# Sheet2.net
KiCad netlist of a schematic drawn in Altium Designer
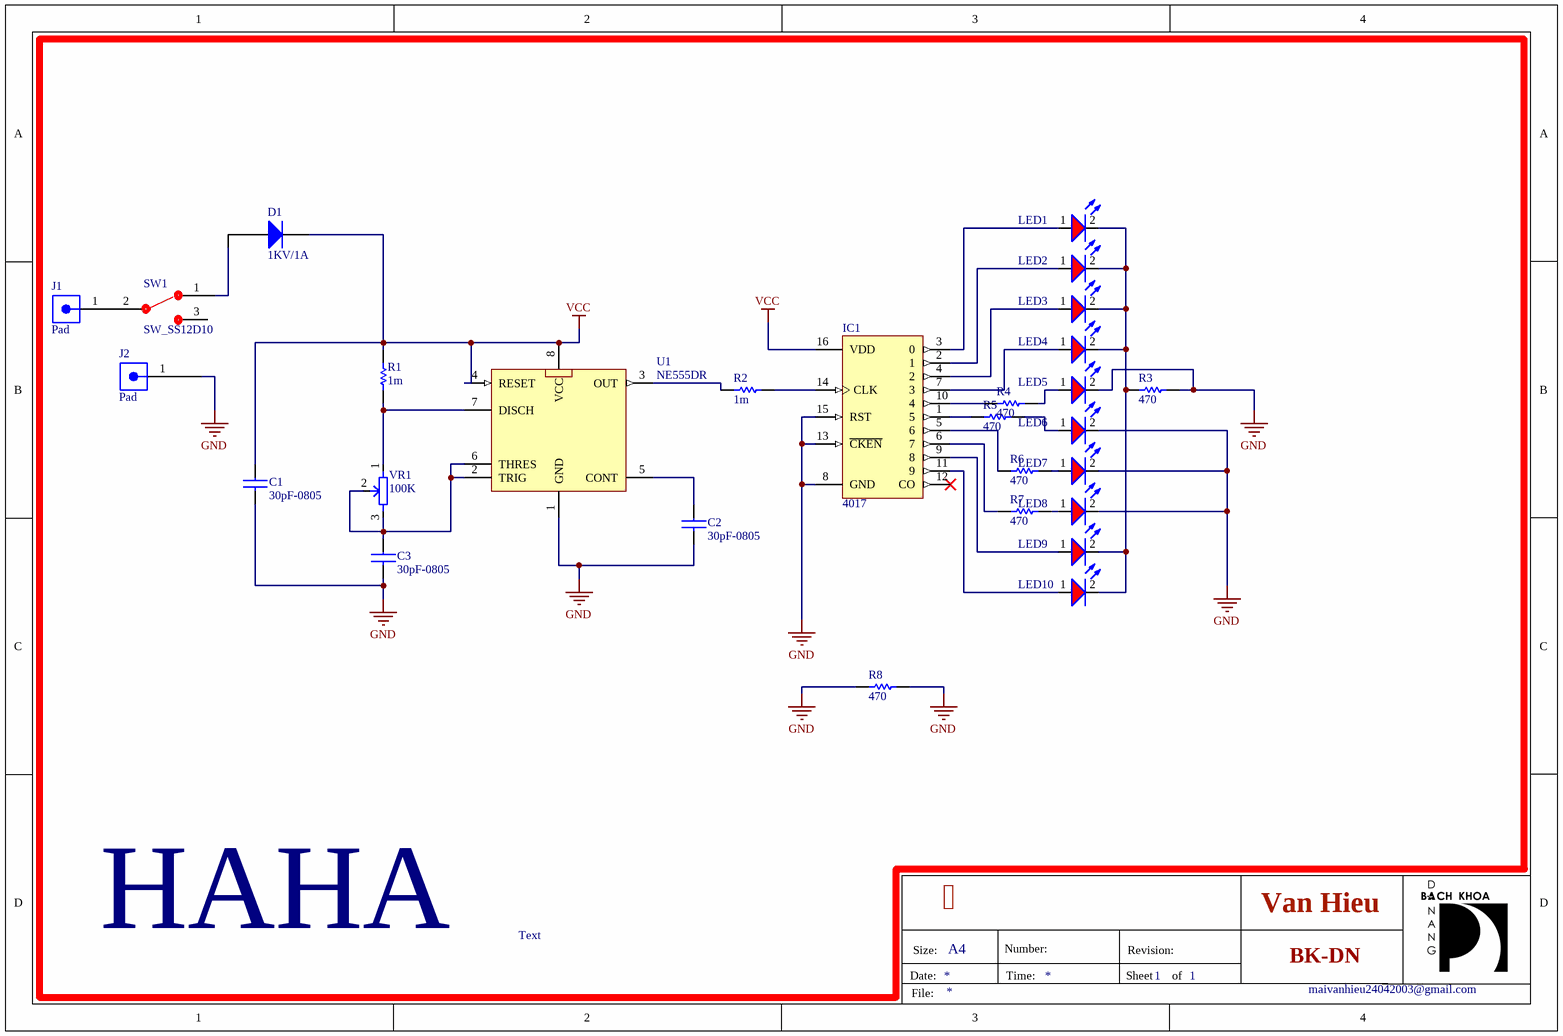
[diagram p0: Sheet2.SchDoc]

(export (version "E")
  (design (tool "Eeschema 10.0.6"))
  (components
    (comp (ref "C1")
      (value "30pF-0805")
      (footprint "CAP0805")
      (description "CAP CER 30PF 50V NPO 0805")
      (fields
        (field (name "MANUFACTURER") "Yageo")
        (field (name "MANUFACTURER PART NUMBER") "CC0805JRNPO9BN300")
      )
      (libsource (lib "Indruino") (part "CC0805JRNPO9BN300"))
    )
    (comp (ref "C2")
      (value "30pF-0805")
      (footprint "CAP0805")
      (description "CAP CER 30PF 50V NPO 0805")
      (fields
        (field (name "MANUFACTURER") "Yageo")
        (field (name "MANUFACTURER PART NUMBER") "CC0805JRNPO9BN300")
      )
      (libsource (lib "Indruino") (part "CC0805JRNPO9BN300"))
    )
    (comp (ref "C3")
      (value "30pF-0805")
      (footprint "CAP0805")
      (description "CAP CER 30PF 50V NPO 0805")
      (fields
        (field (name "MANUFACTURER") "Yageo")
        (field (name "MANUFACTURER PART NUMBER") "CC0805JRNPO9BN300")
      )
      (libsource (lib "Indruino") (part "CC0805JRNPO9BN300"))
    )
    (comp (ref "D1")
      (value "1KV/1A")
      (footprint "DIO-DO41(DO-204AL)-10P-THR")
      (description "DIO GEN 1000V 1A DO41 THR")
      (fields (field (name "MFR") "NA"))
      (libsource (lib "BCLib") (part "SMC-1N4007"))
    )
    (comp (ref "IC1")
      (value "4017")
      (footprint "DIP16/W0.3")
      (description "Decade Counter/Divider with 10 Decoded Outputs")
      (fields (field (name "DESIGNED BY") "VanDungEvn"))
      (libsource (lib "syhaunguyen") (part "4017"))
    )
    (comp (ref "J1")
      (value "Pad")
      (footprint "MinhTien_PcbLib:pad_smd_2x3")
      (fields (field (name "PUBLISHER") "Altium Limited"))
      (libsource (lib "MinhTien_SCHLib") (part "Pad"))
    )
    (comp (ref "J2")
      (value "Pad")
      (footprint "MinhTien_PcbLib:pad_smd_2x3")
      (fields (field (name "PUBLISHER") "Altium Limited"))
      (libsource (lib "MinhTien_SCHLib") (part "Pad"))
    )
    (comp (ref "LED1")
      (value "LED_R_5")
      (footprint "LED5R")
      (description "LED Red 5mm")
      (libsource (lib "lpson") (part "LED_RED_5MM"))
    )
    (comp (ref "LED2")
      (value "LED_R_5")
      (footprint "LED5R")
      (description "LED Red 5mm")
      (libsource (lib "lpson") (part "LED_RED_5MM"))
    )
    (comp (ref "LED3")
      (value "LED_R_5")
      (footprint "LED5R")
      (description "LED Red 5mm")
      (libsource (lib "lpson") (part "LED_RED_5MM"))
    )
    (comp (ref "LED4")
      (value "LED_R_5")
      (footprint "LED5R")
      (description "LED Red 5mm")
      (libsource (lib "lpson") (part "LED_RED_5MM"))
    )
    (comp (ref "LED5")
      (value "LED_R_5")
      (footprint "LED5R")
      (description "LED Red 5mm")
      (libsource (lib "lpson") (part "LED_RED_5MM"))
    )
    (comp (ref "LED6")
      (value "LED_R_5")
      (footprint "LED5R")
      (description "LED Red 5mm")
      (libsource (lib "lpson") (part "LED_RED_5MM"))
    )
    (comp (ref "LED7")
      (value "LED_R_5")
      (footprint "LED5R")
      (description "LED Red 5mm")
      (libsource (lib "lpson") (part "LED_RED_5MM"))
    )
    (comp (ref "LED8")
      (value "LED_R_5")
      (footprint "LED5R")
      (description "LED Red 5mm")
      (libsource (lib "lpson") (part "LED_RED_5MM"))
    )
    (comp (ref "LED9")
      (value "LED_R_5")
      (footprint "LED5R")
      (description "LED Red 5mm")
      (libsource (lib "lpson") (part "LED_RED_5MM"))
    )
    (comp (ref "LED10")
      (value "LED_R_5")
      (footprint "LED5R")
      (description "LED Red 5mm")
      (libsource (lib "lpson") (part "LED_RED_5MM"))
    )
    (comp (ref "R1")
      (value "1m")
      (footprint "MinhTien_PcbLib:RESC2012L")
      (description "Semiconductor Resistor")
      (fields (field (name "Comment") "Resistor 10K-0805") (field (name "PUBLISHER") "Altium Limited"))
      (libsource (lib "MinhTien_SCHLib") (part "Resistor"))
    )
    (comp (ref "R2")
      (value "1m")
      (footprint "MinhTien_PcbLib:RESC2012L")
      (description "Semiconductor Resistor")
      (fields (field (name "Comment") "Resistor 10K-0805") (field (name "PUBLISHER") "Altium Limited"))
      (libsource (lib "MinhTien_SCHLib") (part "Resistor"))
    )
    (comp (ref "R3")
      (value "470")
      (footprint "RES 1/4W CFR25")
      (fields (field (name "Comment") "CF1/4W1KJ25"))
      (libsource (lib "lpson") (part "CF1/4W1KJ25"))
    )
    (comp (ref "R4")
      (value "470")
      (footprint "RES 1/4W CFR25")
      (fields (field (name "Comment") "CF1/4W1KJ25"))
      (libsource (lib "lpson") (part "CF1/4W1KJ25"))
    )
    (comp (ref "R5")
      (value "470")
      (footprint "RES 1/4W CFR25")
      (fields (field (name "Comment") "CF1/4W1KJ25"))
      (libsource (lib "lpson") (part "CF1/4W1KJ25"))
    )
    (comp (ref "R6")
      (value "470")
      (footprint "RES 1/4W CFR25")
      (fields (field (name "Comment") "CF1/4W1KJ25"))
      (libsource (lib "lpson") (part "CF1/4W1KJ25"))
    )
    (comp (ref "R7")
      (value "470")
      (footprint "RES 1/4W CFR25")
      (fields (field (name "Comment") "CF1/4W1KJ25"))
      (libsource (lib "lpson") (part "CF1/4W1KJ25"))
    )
    (comp (ref "R8")
      (value "470")
      (footprint "RES 1/4W CFR25")
      (fields (field (name "Comment") "CF1/4W1KJ25"))
      (libsource (lib "lpson") (part "CF1/4W1KJ25"))
    )
    (comp (ref "SW1")
      (value "SW_SS12D10")
      (footprint "VanHieuLib:SW_SS12D10")
      (description "CONG TAC GAT LON_HIEULIB")
      (libsource (lib "VanHieuLib") (part "SW_SS12D10"))
    )
    (comp (ref "U1")
      (value "NE555DR")
      (footprint "SOIC-8")
      (description "Timers & Support Products Precision")
      (fields (field (name "MANUFACTURER") "Texas Instruments"))
      (libsource (lib "Indruino") (part "NE555DR"))
    )
    (comp (ref "VR1")
      (value "100K")
      (footprint "Bien Tro Tam Giac Dung")
      (description "Cắm")
      (libsource (lib "Altium_Lib_by_KhueNguyenCreator") (part "Bien tro tam giac 100K Dung"))
    )
  )
  (nets
    (net (code "1") (name "GND") (class "Default")
      (node (ref "C1") (pin "2") (pinfunction "2_2") (pintype "passive"))
      (node (ref "C2") (pin "2") (pinfunction "2_2") (pintype "passive"))
      (node (ref "C3") (pin "2") (pinfunction "2_2") (pintype "passive"))
      (node (ref "IC1") (pin "13") (pinfunction "~{CKEN}_13") (pintype "input"))
      (node (ref "IC1") (pin "15") (pinfunction "RST_15") (pintype "input"))
      (node (ref "IC1") (pin "8") (pinfunction "GND_8") (pintype "power_in"))
      (node (ref "J2") (pin "1") (pinfunction "1_1") (pintype "passive"))
      (node (ref "LED5") (pin "2") (pinfunction "K_2") (pintype "passive"))
      (node (ref "LED6") (pin "2") (pinfunction "K_2") (pintype "passive"))
      (node (ref "LED7") (pin "2") (pinfunction "K_2") (pintype "passive"))
      (node (ref "LED8") (pin "2") (pinfunction "K_2") (pintype "passive"))
      (node (ref "R3") (pin "1") (pinfunction "1_1") (pintype "passive"))
      (node (ref "R8") (pin "1") (pinfunction "1_1") (pintype "passive"))
      (node (ref "R8") (pin "2") (pinfunction "2_2") (pintype "passive"))
      (node (ref "U1") (pin "1") (pinfunction "GND_1") (pintype "power_in"))
    )
    (net (code "2") (name "Net-(D1-A)") (class "Default")
      (node (ref "D1") (pin "1") (pinfunction "A_1") (pintype "passive"))
      (node (ref "SW1") (pin "1") (pinfunction "1_1") (pintype "passive"))
    )
    (net (code "3") (name "Net-(IC1-0)") (class "Default")
      (node (ref "IC1") (pin "3") (pinfunction "0_3") (pintype "output"))
      (node (ref "LED1") (pin "1") (pinfunction "A_1") (pintype "passive"))
    )
    (net (code "4") (name "Net-(IC1-1)") (class "Default")
      (node (ref "IC1") (pin "2") (pinfunction "1_2") (pintype "output"))
      (node (ref "LED2") (pin "1") (pinfunction "A_1") (pintype "passive"))
    )
    (net (code "5") (name "Net-(IC1-2)") (class "Default")
      (node (ref "IC1") (pin "4") (pinfunction "2_4") (pintype "output"))
      (node (ref "LED3") (pin "1") (pinfunction "A_1") (pintype "passive"))
    )
    (net (code "6") (name "Net-(IC1-3)") (class "Default")
      (node (ref "IC1") (pin "7") (pinfunction "3_7") (pintype "output"))
      (node (ref "LED4") (pin "1") (pinfunction "A_1") (pintype "passive"))
    )
    (net (code "7") (name "Net-(IC1-4)") (class "Default")
      (node (ref "IC1") (pin "10") (pinfunction "4_10") (pintype "output"))
      (node (ref "R4") (pin "2") (pinfunction "2_2") (pintype "passive"))
    )
    (net (code "8") (name "Net-(IC1-5)") (class "Default")
      (node (ref "IC1") (pin "1") (pinfunction "5_1") (pintype "output"))
      (node (ref "R5") (pin "2") (pinfunction "2_2") (pintype "passive"))
    )
    (net (code "9") (name "Net-(IC1-6)") (class "Default")
      (node (ref "IC1") (pin "5") (pinfunction "6_5") (pintype "output"))
      (node (ref "R6") (pin "2") (pinfunction "2_2") (pintype "passive"))
    )
    (net (code "10") (name "Net-(IC1-7)") (class "Default")
      (node (ref "IC1") (pin "6") (pinfunction "7_6") (pintype "output"))
      (node (ref "R7") (pin "2") (pinfunction "2_2") (pintype "passive"))
    )
    (net (code "11") (name "Net-(IC1-8)") (class "Default")
      (node (ref "IC1") (pin "9") (pinfunction "8_9") (pintype "output"))
      (node (ref "LED9") (pin "1") (pinfunction "A_1") (pintype "passive"))
    )
    (net (code "12") (name "Net-(IC1-9)") (class "Default")
      (node (ref "IC1") (pin "11") (pinfunction "9_11") (pintype "output"))
      (node (ref "LED10") (pin "1") (pinfunction "A_1") (pintype "passive"))
    )
    (net (code "13") (name "Net-(IC1-CLK)") (class "Default")
      (node (ref "IC1") (pin "14") (pinfunction "CLK_14") (pintype "input"))
      (node (ref "R2") (pin "1") (pinfunction "1_1") (pintype "passive"))
    )
    (net (code "14") (name "Net-(J1-Pad1)") (class "Default")
      (node (ref "J1") (pin "1") (pinfunction "1_1") (pintype "passive"))
      (node (ref "SW1") (pin "2") (pinfunction "2_2") (pintype "passive"))
    )
    (net (code "15") (name "Net-(LED1-K)") (class "Default")
      (node (ref "LED1") (pin "2") (pinfunction "K_2") (pintype "passive"))
      (node (ref "LED10") (pin "2") (pinfunction "K_2") (pintype "passive"))
      (node (ref "LED2") (pin "2") (pinfunction "K_2") (pintype "passive"))
      (node (ref "LED3") (pin "2") (pinfunction "K_2") (pintype "passive"))
      (node (ref "LED4") (pin "2") (pinfunction "K_2") (pintype "passive"))
      (node (ref "LED9") (pin "2") (pinfunction "K_2") (pintype "passive"))
      (node (ref "R3") (pin "2") (pinfunction "2_2") (pintype "passive"))
    )
    (net (code "16") (name "Net-(LED5-A)") (class "Default")
      (node (ref "LED5") (pin "1") (pinfunction "A_1") (pintype "passive"))
      (node (ref "R4") (pin "1") (pinfunction "1_1") (pintype "passive"))
    )
    (net (code "17") (name "Net-(LED6-A)") (class "Default")
      (node (ref "LED6") (pin "1") (pinfunction "A_1") (pintype "passive"))
      (node (ref "R5") (pin "1") (pinfunction "1_1") (pintype "passive"))
    )
    (net (code "18") (name "Net-(LED7-A)") (class "Default")
      (node (ref "LED7") (pin "1") (pinfunction "A_1") (pintype "passive"))
      (node (ref "R6") (pin "1") (pinfunction "1_1") (pintype "passive"))
    )
    (net (code "19") (name "Net-(LED8-A)") (class "Default")
      (node (ref "LED8") (pin "1") (pinfunction "A_1") (pintype "passive"))
      (node (ref "R7") (pin "1") (pinfunction "1_1") (pintype "passive"))
    )
    (net (code "20") (name "Net-(U1-CONT)") (class "Default")
      (node (ref "C2") (pin "1") (pinfunction "1_1") (pintype "passive"))
      (node (ref "U1") (pin "5") (pinfunction "CONT_5") (pintype "passive"))
    )
    (net (code "21") (name "Net-(U1-DISCH)") (class "Default")
      (node (ref "R1") (pin "1") (pinfunction "1_1") (pintype "passive"))
      (node (ref "U1") (pin "7") (pinfunction "DISCH_7") (pintype "passive"))
      (node (ref "VR1") (pin "1") (pinfunction "1_1") (pintype "passive"))
    )
    (net (code "22") (name "Net-(U1-OUT)") (class "Default")
      (node (ref "R2") (pin "2") (pinfunction "2_2") (pintype "passive"))
      (node (ref "U1") (pin "3") (pinfunction "OUT_3") (pintype "output"))
    )
    (net (code "23") (name "Net-(U1-THRES)") (class "Default")
      (node (ref "C3") (pin "1") (pinfunction "1_1") (pintype "passive"))
      (node (ref "U1") (pin "2") (pinfunction "TRIG_2") (pintype "passive"))
      (node (ref "U1") (pin "6") (pinfunction "THRES_6") (pintype "passive"))
      (node (ref "VR1") (pin "2") (pinfunction "2_2") (pintype "passive"))
      (node (ref "VR1") (pin "3") (pinfunction "3_3") (pintype "passive"))
    )
    (net (code "24") (name "VCC") (class "Default")
      (node (ref "C1") (pin "1") (pinfunction "1_1") (pintype "passive"))
      (node (ref "D1") (pin "2") (pinfunction "K_2") (pintype "passive"))
      (node (ref "IC1") (pin "16") (pinfunction "VDD_16") (pintype "power_in"))
      (node (ref "R1") (pin "2") (pinfunction "2_2") (pintype "passive"))
      (node (ref "U1") (pin "4") (pinfunction "RESET_4") (pintype "input"))
      (node (ref "U1") (pin "8") (pinfunction "VCC_8") (pintype "power_in"))
    )
    (net (code "25") (name "unconnected-(IC1-CO-Pad12)") (class "Default")
      (node (ref "IC1") (pin "12") (pinfunction "CO_12") (pintype "output+no_connect"))
    )
    (net (code "26") (name "unconnected-(SW1-Pad3)") (class "Default")
      (node (ref "SW1") (pin "3") (pinfunction "3_3") (pintype "passive"))
    )
  )
)
